# Haptic.net
KiCad netlist of a schematic drawn in Altium Designer
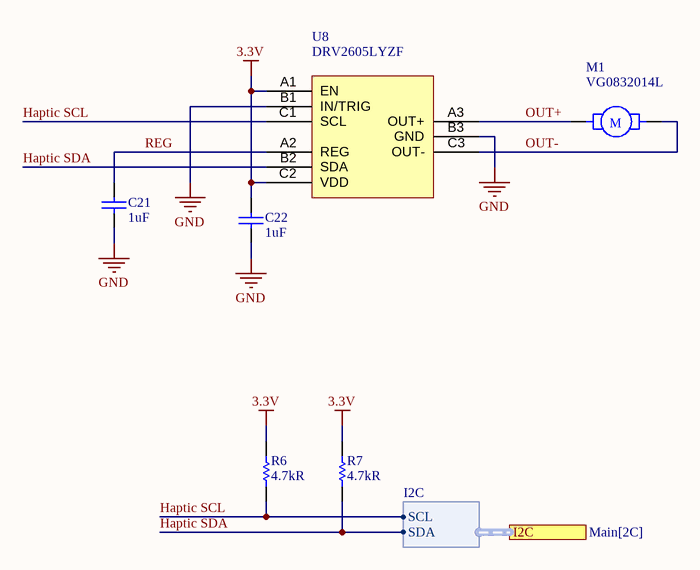
[diagram p0: Haptic.SchDoc]

(export (version "E")
  (design (tool "Eeschema 10.0.6"))
  (components
    (comp (ref "C21") (value "1uF") (footprint "Capacitor 0402") (libsource (lib "x-io") (part "Capacitor")))
    (comp (ref "C22") (value "1uF") (footprint "Capacitor 0402") (libsource (lib "x-io") (part "Capacitor")))
    (comp (ref "M1")
      (value "VG0832014L")
      (footprint "VG0832014L")
      (libsource (lib "x-io") (part "VG0832014L"))
    )
    (comp (ref "R6") (value "4.7kR") (footprint "Resistor 0402") (libsource (lib "x-io") (part "Resistor")))
    (comp (ref "R7") (value "4.7kR") (footprint "Resistor 0402") (libsource (lib "x-io") (part "Resistor")))
    (comp (ref "U8")
      (value "DRV2605LYZF")
      (footprint "DRV2605LYZF")
      (libsource (lib "x-io") (part "DRV2605LYZF"))
    )
  )
  (nets
    (net (code "2") (name "/Haptic SCL") (class "Default")
      (node (ref "R6") (pin "1") (pinfunction "1_1") (pintype "passive"))
      (node (ref "U8") (pin "C1") (pinfunction "SCL_C1") (pintype "passive"))
    )
    (net (code "3") (name "/Haptic SDA") (class "Default")
      (node (ref "R7") (pin "1") (pinfunction "1_1") (pintype "passive"))
      (node (ref "U8") (pin "B2") (pinfunction "SDA_B2") (pintype "passive"))
    )
    (net (code "4") (name "/OUT+") (class "Default")
      (node (ref "M1") (pin "1") (pinfunction "1_1") (pintype "passive"))
      (node (ref "U8") (pin "A3") (pinfunction "OUT+_A3") (pintype "passive"))
    )
    (net (code "5") (name "/OUT-") (class "Default")
      (node (ref "M1") (pin "2") (pinfunction "2_2") (pintype "passive"))
      (node (ref "U8") (pin "C3") (pinfunction "OUT-_C3") (pintype "passive"))
    )
    (net (code "6") (name "/REG") (class "Default")
      (node (ref "C21") (pin "2") (pinfunction "2_2") (pintype "passive"))
      (node (ref "U8") (pin "A2") (pinfunction "REG_A2") (pintype "passive"))
    )
    (net (code "8") (name "3.3V") (class "Default")
      (node (ref "C22") (pin "2") (pinfunction "2_2") (pintype "passive"))
      (node (ref "R6") (pin "2") (pinfunction "2_2") (pintype "passive"))
      (node (ref "R7") (pin "2") (pinfunction "2_2") (pintype "passive"))
      (node (ref "U8") (pin "A1") (pinfunction "EN_A1") (pintype "passive"))
      (node (ref "U8") (pin "C2") (pinfunction "VDD_C2") (pintype "passive"))
    )
    (net (code "9") (name "GND") (class "Default")
      (node (ref "C21") (pin "1") (pinfunction "1_1") (pintype "passive"))
      (node (ref "C22") (pin "1") (pinfunction "1_1") (pintype "passive"))
      (node (ref "U8") (pin "B1") (pinfunction "IN/TRIG_B1") (pintype "passive"))
      (node (ref "U8") (pin "B3") (pinfunction "GND_B3") (pintype "passive"))
    )
  )
)
